# Red_Light_Check.net
KiCad netlist of a schematic drawn in Altium Designer
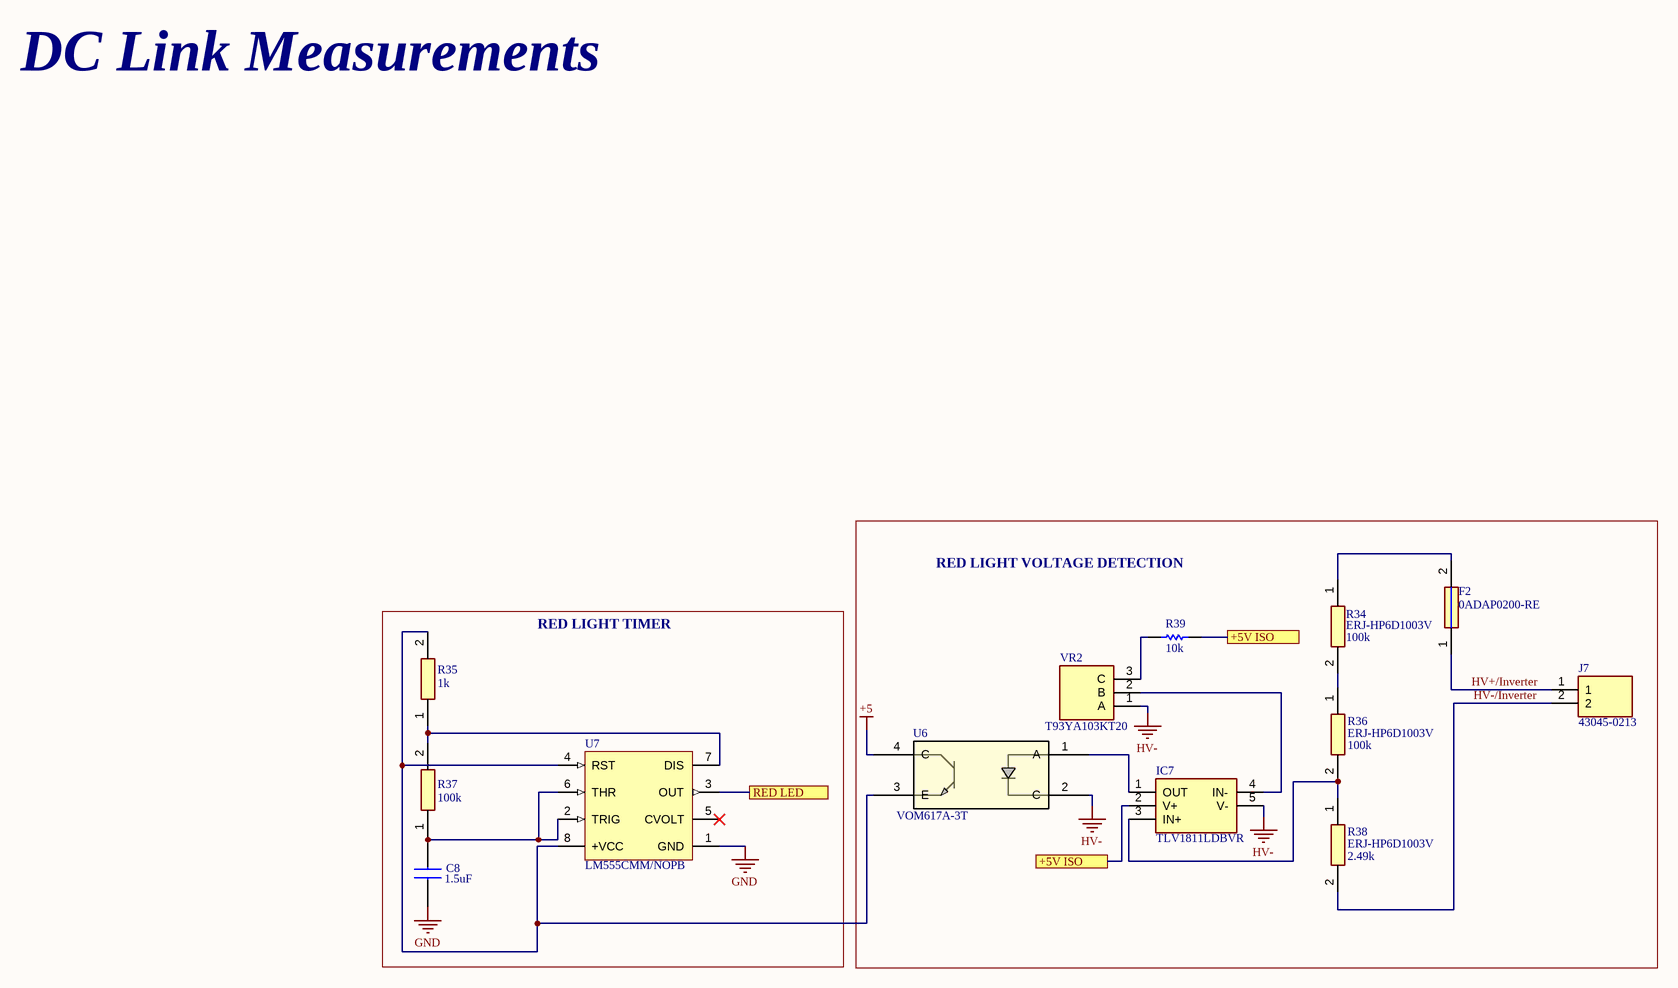
[diagram p0: Red_Light_Check.SchDoc]

(export (version "E")
  (design (tool "Eeschema 10.0.6"))
  (components
    (comp (ref "C8")
      (value "C1005X6S0G155M050BC")
      (footprint "CAPC1005X55N")
      (description "MULTILAYER CERAMIC CHIP CAPACITORS, 1005, Commercial grade, general (Up to 75V)")
      (libsource (lib "C1005X6S0G155M050BC") (part "C1005X6S0G155M050BC"))
    )
    (comp (ref "F2")
      (value "0ADAP0200-RE")
      (footprint "SamacSys:0ADAP0200RE")
      (description "Fuse")
      (fields (field (name "MOUSER PART NUMBER") "530-0ADAP0200-RE"))
      (libsource (lib "*") (part "0ADAP0200-RE"))
    )
    (comp (ref "IC7")
      (value "TLV1811LDBVR")
      (footprint "SamacSys:SOT95P280X145-5N")
      (description "Integrated Circuit")
      (fields (field (name "MOUSER PART NUMBER") "595-TLV1811LDBVR"))
      (libsource (lib "*") (part "TLV1811LDBVR"))
    )
    (comp (ref "J7")
      (value "43045-0213")
      (footprint "SamacSys:43045-02YY_121314")
      (description "Connector")
      (fields (field (name "MOUSER PART NUMBER") "538-43045-0213"))
      (libsource (lib "*") (part "43045-0213"))
    )
    (comp (ref "R34")
      (value "ERJ-HP6D1003V")
      (footprint "ERJHP6D1000V")
      (description "Resistor")
      (libsource (lib "EMEA- Poseidon Team- University of West Attica") (part "CRCW080549R9FKEAHP"))
    )
    (comp (ref "R35")
      (value "RA73F1J1K0BTDF")
      (footprint "SamacSys:RESC1608X58N")
      (description "Resistor")
      (fields (field (name "MOUSER PART NUMBER") "279-RA73F1J1K0BTDF"))
      (libsource (lib "*") (part "RA73F1J1K0BTDF"))
    )
    (comp (ref "R36")
      (value "ERJ-HP6D1003V")
      (footprint "ERJHP6D1000V")
      (description "Resistor")
      (libsource (lib "EMEA- Poseidon Team- University of West Attica") (part "CRCW080549R9FKEAHP"))
    )
    (comp (ref "R37")
      (value "RK73H2ATTD1003F")
      (footprint "SamacSys:RESC2012X60N")
      (description "Resistor")
      (fields (field (name "MOUSER PART NUMBER") "660-RK73H2ATTD1003F"))
      (libsource (lib "*") (part "RK73H2ATTD1003F"))
    )
    (comp (ref "R38")
      (value "ERJ-HP6D1003V")
      (footprint "ERJHP6D1000V")
      (description "Resistor")
      (libsource (lib "EMEA- Poseidon Team- University of West Attica") (part "CRCW080549R9FKEAHP"))
    )
    (comp (ref "R39")
      (value "CRCW080510K0FKEC")
      (footprint "RESC2013X50X30ML20T20")
      (fields (field (name "MANUFACTURER") "Vishay Dale"))
      (libsource (lib "Altium Content Vault") (part "RES"))
    )
    (comp (ref "U6")
      (value "VOM617A-3T")
      (footprint "SMD-4_VOM617A_VIS")
      (description "VOM617A-3T Transistor Output Optocoupler, 1-Element, 3750V Isolation")
      (libsource (lib "Altium Content Vault") (part "VOM617A-3T"))
    )
    (comp (ref "U7")
      (value "LM555CMM/NOPB")
      (footprint "DGK0008A_N")
      (description "Timer, 8-pin Mini SOIC, Pb-Free")
      (fields (field (name "MANUFACTURER") "Texas Instruments"))
      (libsource (lib "Altium Content Vault") (part "AN-TIMER-LM555-8"))
    )
    (comp (ref "VR2")
      (value "T93YA103KT20")
      (footprint "SamacSys:T93YA5K10")
      (description "Variable Resistor")
      (fields (field (name "MOUSER PART NUMBER") "72-T93YA-10K"))
      (libsource (lib "*") (part "T93YA103KT20"))
    )
  )
  (nets
    (net (code "1") (name "+5") (class "Default")
      (node (ref "U6") (pin "4") (pinfunction "C_4") (pintype "passive"))
    )
    (net (code "2") (name "/+5V ISO") (class "Default")
      (node (ref "IC7") (pin "2") (pinfunction "V+_2") (pintype "passive"))
      (node (ref "R39") (pin "1") (pinfunction "1_1") (pintype "passive"))
    )
    (net (code "3") (name "/HV+{slash}Inverter") (class "Default")
      (node (ref "F2") (pin "1") (pinfunction "1_1") (pintype "passive"))
      (node (ref "J7") (pin "1") (pinfunction "1_1") (pintype "passive"))
    )
    (net (code "4") (name "/HV-{slash}Inverter") (class "Default")
      (node (ref "J7") (pin "2") (pinfunction "2_2") (pintype "passive"))
      (node (ref "R38") (pin "2") (pinfunction "2_2") (pintype "passive"))
    )
    (net (code "5") (name "/RED LED") (class "Default")
      (node (ref "U7") (pin "3") (pinfunction "OUT_3") (pintype "output"))
    )
    (net (code "6") (name "GND") (class "Default")
      (node (ref "C8") (pin "1") (pinfunction "1_1") (pintype "passive"))
      (node (ref "U7") (pin "1") (pinfunction "GND_1") (pintype "power_in"))
    )
    (net (code "7") (name "HV-") (class "Default")
      (node (ref "IC7") (pin "5") (pinfunction "V-_5") (pintype "passive"))
      (node (ref "U6") (pin "2") (pinfunction "C_2") (pintype "passive"))
      (node (ref "VR2") (pin "1") (pinfunction "A_1") (pintype "passive"))
    )
    (net (code "8") (name "Net-(F2-Pad2)") (class "Default")
      (node (ref "F2") (pin "2") (pinfunction "2_2") (pintype "passive"))
      (node (ref "R34") (pin "1") (pinfunction "1_1") (pintype "passive"))
    )
    (net (code "9") (name "Net-(IC7-IN+)") (class "Default")
      (node (ref "IC7") (pin "3") (pinfunction "IN+_3") (pintype "passive"))
      (node (ref "R36") (pin "2") (pinfunction "2_2") (pintype "passive"))
      (node (ref "R38") (pin "1") (pinfunction "1_1") (pintype "passive"))
    )
    (net (code "10") (name "Net-(IC7-IN-)") (class "Default")
      (node (ref "IC7") (pin "4") (pinfunction "IN-_4") (pintype "passive"))
      (node (ref "VR2") (pin "2") (pinfunction "B_2") (pintype "passive"))
    )
    (net (code "11") (name "Net-(IC7-OUT)") (class "Default")
      (node (ref "IC7") (pin "1") (pinfunction "OUT_1") (pintype "passive"))
      (node (ref "U6") (pin "1") (pinfunction "A_1") (pintype "passive"))
    )
    (net (code "12") (name "Net-(R34-Pad2)") (class "Default")
      (node (ref "R34") (pin "2") (pinfunction "2_2") (pintype "passive"))
      (node (ref "R36") (pin "1") (pinfunction "1_1") (pintype "passive"))
    )
    (net (code "13") (name "Net-(U6-E)") (class "Default")
      (node (ref "R35") (pin "2") (pinfunction "2_2") (pintype "passive"))
      (node (ref "U6") (pin "3") (pinfunction "E_3") (pintype "passive"))
      (node (ref "U7") (pin "4") (pinfunction "RST_4") (pintype "input"))
      (node (ref "U7") (pin "8") (pinfunction "+VCC_8") (pintype "power_in"))
    )
    (net (code "14") (name "Net-(U7-DIS)") (class "Default")
      (node (ref "R35") (pin "1") (pinfunction "1_1") (pintype "passive"))
      (node (ref "R37") (pin "2") (pinfunction "2_2") (pintype "passive"))
      (node (ref "U7") (pin "7") (pinfunction "DIS_7") (pintype "open_collector"))
    )
    (net (code "15") (name "Net-(U7-THR)") (class "Default")
      (node (ref "C8") (pin "2") (pinfunction "2_2") (pintype "passive"))
      (node (ref "R37") (pin "1") (pinfunction "1_1") (pintype "passive"))
      (node (ref "U7") (pin "2") (pinfunction "TRIG_2") (pintype "input"))
      (node (ref "U7") (pin "6") (pinfunction "THR_6") (pintype "input"))
    )
    (net (code "16") (name "Net-(VR2-C)") (class "Default")
      (node (ref "R39") (pin "2") (pinfunction "2_2") (pintype "passive"))
      (node (ref "VR2") (pin "3") (pinfunction "C_3") (pintype "passive"))
    )
    (net (code "17") (name "unconnected-(U7-CVOLT-Pad5)") (class "Default")
      (node (ref "U7") (pin "5") (pinfunction "CVOLT_5") (pintype "passive+no_connect"))
    )
  )
)
